# boilup_v2.net
KiCad netlist of a schematic drawn in EAGLE
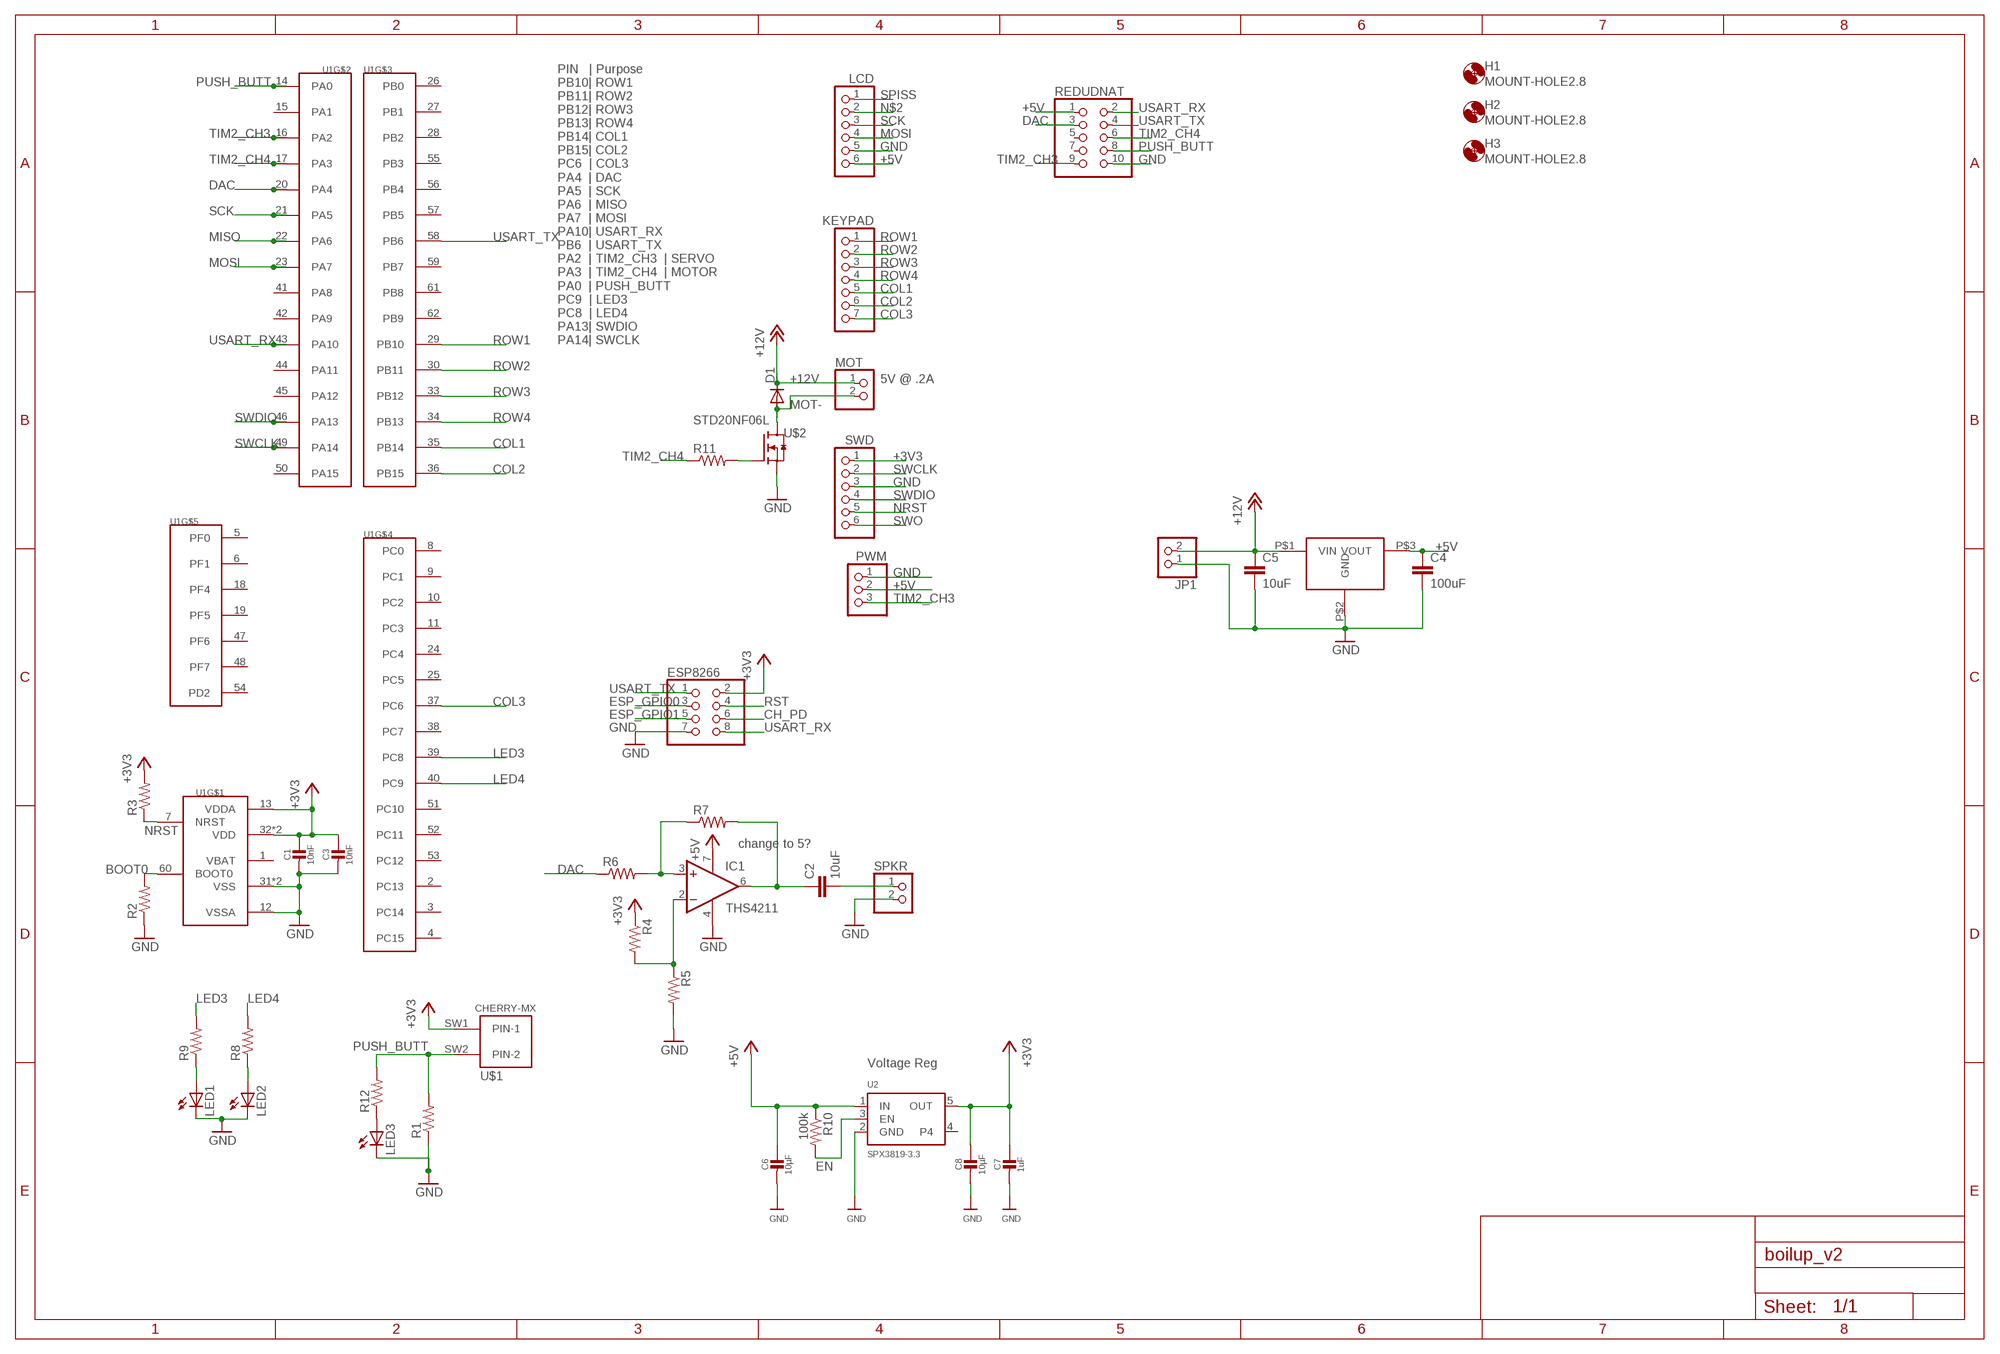
[diagram p0: schematic, sheet 1]

(export (version "E")
  (design (tool "Eeschema 10.0.6"))
  (components
    (comp (ref "C1")
      (value "10nF")
      (footprint "eagle-import:0805-NO")
      (libsource (lib "eagle-import") (part "CAP_CERAMIC0805-NOOUTLINE"))
    )
    (comp (ref "C2")
      (value "10uF")
      (footprint "eagle-import:C0603K")
      (libsource (lib "eagle-import") (part "C-EUC0603K"))
    )
    (comp (ref "C3")
      (value "10nF")
      (footprint "eagle-import:0805-NO")
      (libsource (lib "eagle-import") (part "CAP_CERAMIC0805-NOOUTLINE"))
    )
    (comp (ref "C4")
      (value "100uF")
      (footprint "eagle-import:C1210K")
      (libsource (lib "eagle-import") (part "C-EUC1210K"))
    )
    (comp (ref "C5")
      (value "10uF")
      (footprint "eagle-import:C0603K")
      (libsource (lib "eagle-import") (part "C-EUC0603K"))
    )
    (comp (ref "C6")
      (value "10µF")
      (footprint "eagle-import:0805-NO")
      (libsource (lib "eagle-import") (part "CAP_CERAMIC0805-NOOUTLINE"))
    )
    (comp (ref "C7")
      (value "1uF")
      (footprint "eagle-import:0603-NO")
      (libsource (lib "eagle-import") (part "CAP_CERAMIC0603_NO"))
    )
    (comp (ref "C8")
      (value "10µF")
      (footprint "eagle-import:0805-NO")
      (libsource (lib "eagle-import") (part "CAP_CERAMIC0805-NOOUTLINE"))
    )
    (comp (ref "D1")
      (value "DIODE-DO-214AC")
      (footprint "eagle-import:DO-214AC")
      (libsource (lib "eagle-import") (part "DIODE-DO-214AC"))
    )
    (comp (ref "ESP8266")
      (value "PINHD-2X4")
      (footprint "eagle-import:2X04")
      (libsource (lib "eagle-import") (part "PINHD-2X4"))
    )
    (comp (ref "H1")
      (value "MOUNT-HOLE2.8")
      (footprint "eagle-import:2,8")
      (libsource (lib "eagle-import") (part "MOUNT-HOLE2.8"))
    )
    (comp (ref "H2")
      (value "MOUNT-HOLE2.8")
      (footprint "eagle-import:2,8")
      (libsource (lib "eagle-import") (part "MOUNT-HOLE2.8"))
    )
    (comp (ref "H3")
      (value "MOUNT-HOLE2.8")
      (footprint "eagle-import:2,8")
      (libsource (lib "eagle-import") (part "MOUNT-HOLE2.8"))
    )
    (comp (ref "IC1")
      (value "THS4211")
      (footprint "eagle-import:S-PDSO-G08")
      (fields (field (name "MF") "TEXAS INSTRUMENT CONNECTORS") (field (name "MPN") "THS4211DGK"))
      (libsource (lib "eagle-import") (part "THS4211"))
    )
    (comp (ref "JP1")
      (value "PINHD-1X2")
      (footprint "eagle-import:1X02")
      (libsource (lib "eagle-import") (part "PINHD-1X2"))
    )
    (comp (ref "KEYPAD")
      (value "PINHD-1X7")
      (footprint "eagle-import:1X07")
      (libsource (lib "eagle-import") (part "PINHD-1X7"))
    )
    (comp (ref "LCD")
      (value "PINHD-1X6")
      (footprint "eagle-import:1X06")
      (libsource (lib "eagle-import") (part "PINHD-1X6"))
    )
    (comp (ref "LED1")
      (value "LEDSML0805")
      (footprint "eagle-import:SML0805")
      (libsource (lib "eagle-import") (part "LEDSML0805"))
    )
    (comp (ref "LED2")
      (value "LEDSML0805")
      (footprint "eagle-import:SML0805")
      (libsource (lib "eagle-import") (part "LEDSML0805"))
    )
    (comp (ref "LED3")
      (value "LEDSML0805")
      (footprint "eagle-import:SML0805")
      (libsource (lib "eagle-import") (part "LEDSML0805"))
    )
    (comp (ref "MOT")
      (value "PINHD-1X2")
      (footprint "eagle-import:1X02")
      (libsource (lib "eagle-import") (part "PINHD-1X2"))
    )
    (comp (ref "PWM")
      (value "PINHD-1X3")
      (footprint "eagle-import:1X03")
      (libsource (lib "eagle-import") (part "PINHD-1X3"))
    )
    (comp (ref "R1")
      (value "R-US_R0603")
      (footprint "eagle-import:R0603")
      (libsource (lib "eagle-import") (part "resistor_348_R-US_R0603"))
    )
    (comp (ref "R2")
      (value "R-US_R0603")
      (footprint "eagle-import:R0603")
      (libsource (lib "eagle-import") (part "resistor_348_R-US_R0603"))
    )
    (comp (ref "R3")
      (value "R-US_R0603")
      (footprint "eagle-import:R0603")
      (libsource (lib "eagle-import") (part "resistor_348_R-US_R0603"))
    )
    (comp (ref "R4")
      (value "R-US_R0603")
      (footprint "eagle-import:R0603")
      (libsource (lib "eagle-import") (part "resistor_348_R-US_R0603"))
    )
    (comp (ref "R5")
      (value "R-US_R0603")
      (footprint "eagle-import:R0603")
      (libsource (lib "eagle-import") (part "resistor_348_R-US_R0603"))
    )
    (comp (ref "R6")
      (value "R-US_R0603")
      (footprint "eagle-import:R0603")
      (libsource (lib "eagle-import") (part "resistor_348_R-US_R0603"))
    )
    (comp (ref "R7")
      (value "R-US_R0603")
      (footprint "eagle-import:R0603")
      (libsource (lib "eagle-import") (part "resistor_348_R-US_R0603"))
    )
    (comp (ref "R8")
      (value "R-US_R0603")
      (footprint "eagle-import:R0603")
      (libsource (lib "eagle-import") (part "resistor_348_R-US_R0603"))
    )
    (comp (ref "R9")
      (value "R-US_R0603")
      (footprint "eagle-import:R0603")
      (libsource (lib "eagle-import") (part "resistor_348_R-US_R0603"))
    )
    (comp (ref "R10")
      (value "100k")
      (footprint "eagle-import:R0603")
      (libsource (lib "eagle-import") (part "R-US_R0603"))
    )
    (comp (ref "R11")
      (value "R-US_R0603")
      (footprint "eagle-import:R0603")
      (libsource (lib "eagle-import") (part "resistor_348_R-US_R0603"))
    )
    (comp (ref "R12")
      (value "R-US_R0603")
      (footprint "eagle-import:R0603")
      (libsource (lib "eagle-import") (part "resistor_348_R-US_R0603"))
    )
    (comp (ref "REDUDNAT")
      (value "PINHD-2X5")
      (footprint "eagle-import:2X05")
      (libsource (lib "eagle-import") (part "PINHD-2X5"))
    )
    (comp (ref "SPKR")
      (value "PINHD-1X2")
      (footprint "eagle-import:1X02")
      (libsource (lib "eagle-import") (part "PINHD-1X2"))
    )
    (comp (ref "SWD")
      (value "PINHD-1X6")
      (footprint "eagle-import:1X06")
      (libsource (lib "eagle-import") (part "PINHD-1X6"))
    )
    (comp (ref "U$1")
      (value "CHERRY-MX")
      (footprint "eagle-import:CHERRY-MX")
      (libsource (lib "eagle-import") (part "CHERRY-MX"))
    )
    (comp (ref "U$2")
      (value "STD20NF06L")
      (footprint "eagle-import:DPAK")
      (libsource (lib "eagle-import") (part "STD20NF06L"))
    )
    (comp (ref "U$3")
      (value "TPSM842")
      (footprint "eagle-import:TO-220")
      (libsource (lib "eagle-import") (part "TPSM842"))
    )
    (comp (ref "U1")
      (value "STM32F0_LQFP64")
      (footprint "eagle-import:QFP50P1200X1200X160-64N")
      (libsource (lib "eagle-import") (part "STM32F0_LQFP64"))
    )
    (comp (ref "U2")
      (value "SPX3819-3.3")
      (footprint "eagle-import:SOT23-5")
      (libsource (lib "eagle-import") (part "VREG_SOT23-5"))
    )
  )
  (nets
    (net (code "1") (name "+3V3") (class "Default")
      (node (ref "C1") (pin "1") (pinfunction "1_1") (pintype "passive"))
      (node (ref "C3") (pin "1") (pinfunction "1_1") (pintype "passive"))
      (node (ref "C7") (pin "1") (pinfunction "1_1") (pintype "passive"))
      (node (ref "C8") (pin "1") (pinfunction "1_1") (pintype "passive"))
      (node (ref "ESP8266") (pin "2") (pinfunction "2_2") (pintype "passive"))
      (node (ref "R3") (pin "2") (pinfunction "2_2") (pintype "passive"))
      (node (ref "R4") (pin "1") (pinfunction "1_1") (pintype "passive"))
      (node (ref "SWD") (pin "1") (pinfunction "1_1") (pintype "passive"))
      (node (ref "U$1") (pin "SW1") (pinfunction "PIN-1_SW1") (pintype "bidirectional"))
      (node (ref "U1") (pin "13") (pinfunction "VDDA_13") (pintype "bidirectional"))
      (node (ref "U1") (pin "32") (pinfunction "VDD_32") (pintype "bidirectional"))
      (node (ref "U1") (pin "64") (pinfunction "VDD_64") (pintype "bidirectional"))
      (node (ref "U2") (pin "5") (pinfunction "OUT_5") (pintype "power_in"))
    )
    (net (code "2") (name "+5V") (class "Default")
      (node (ref "C4") (pin "1") (pinfunction "1_1") (pintype "passive"))
      (node (ref "C6") (pin "1") (pinfunction "1_1") (pintype "passive"))
      (node (ref "IC1") (pin "7") (pinfunction "V+_7") (pintype "power_in"))
      (node (ref "LCD") (pin "6") (pinfunction "6_6") (pintype "passive"))
      (node (ref "PWM") (pin "2") (pinfunction "2_2") (pintype "passive"))
      (node (ref "R10") (pin "1") (pinfunction "1_1") (pintype "passive"))
      (node (ref "REDUDNAT") (pin "1") (pinfunction "1_1") (pintype "passive"))
      (node (ref "U$3") (pin "P$3") (pinfunction "VOUT_P$3") (pintype "bidirectional"))
      (node (ref "U2") (pin "1") (pinfunction "IN_1") (pintype "power_in"))
    )
    (net (code "3") (name "+12V") (class "Default")
      (node (ref "C5") (pin "1") (pinfunction "1_1") (pintype "passive"))
      (node (ref "D1") (pin "C") (pinfunction "C_C") (pintype "passive"))
      (node (ref "JP1") (pin "2") (pinfunction "2_2") (pintype "passive"))
      (node (ref "MOT") (pin "1") (pinfunction "1_1") (pintype "passive"))
      (node (ref "U$3") (pin "P$1") (pinfunction "VIN_P$1") (pintype "bidirectional"))
    )
    (net (code "4") (name "/BOOT0") (class "Default")
      (node (ref "R2") (pin "2") (pinfunction "2_2") (pintype "passive"))
      (node (ref "U1") (pin "60") (pinfunction "BOOT0_60") (pintype "bidirectional"))
    )
    (net (code "5") (name "/CH_PD") (class "Default")
      (node (ref "ESP8266") (pin "6") (pinfunction "6_6") (pintype "passive"))
    )
    (net (code "6") (name "/COL1") (class "Default")
      (node (ref "KEYPAD") (pin "5") (pinfunction "5_5") (pintype "passive"))
      (node (ref "U1") (pin "35") (pinfunction "PB14_35") (pintype "bidirectional"))
    )
    (net (code "7") (name "/COL2") (class "Default")
      (node (ref "KEYPAD") (pin "6") (pinfunction "6_6") (pintype "passive"))
      (node (ref "U1") (pin "36") (pinfunction "PB15_36") (pintype "bidirectional"))
    )
    (net (code "8") (name "/COL3") (class "Default")
      (node (ref "KEYPAD") (pin "7") (pinfunction "7_7") (pintype "passive"))
      (node (ref "U1") (pin "37") (pinfunction "PC6_37") (pintype "bidirectional"))
    )
    (net (code "9") (name "/DAC") (class "Default")
      (node (ref "R6") (pin "1") (pinfunction "1_1") (pintype "passive"))
      (node (ref "REDUDNAT") (pin "3") (pinfunction "3_3") (pintype "passive"))
      (node (ref "U1") (pin "20") (pinfunction "PA4_20") (pintype "bidirectional"))
    )
    (net (code "10") (name "/EN") (class "Default")
      (node (ref "R10") (pin "2") (pinfunction "2_2") (pintype "passive"))
      (node (ref "U2") (pin "3") (pinfunction "EN_3") (pintype "input"))
    )
    (net (code "11") (name "/ESP_GPIO0") (class "Default")
      (node (ref "ESP8266") (pin "3") (pinfunction "3_3") (pintype "passive"))
    )
    (net (code "12") (name "/ESP_GPIO1") (class "Default")
      (node (ref "ESP8266") (pin "5") (pinfunction "5_5") (pintype "passive"))
    )
    (net (code "13") (name "/LED3") (class "Default")
      (node (ref "R9") (pin "2") (pinfunction "2_2") (pintype "passive"))
      (node (ref "U1") (pin "39") (pinfunction "PC8_39") (pintype "bidirectional"))
    )
    (net (code "14") (name "/LED4") (class "Default")
      (node (ref "R8") (pin "2") (pinfunction "2_2") (pintype "passive"))
      (node (ref "U1") (pin "40") (pinfunction "PC9_40") (pintype "bidirectional"))
    )
    (net (code "15") (name "/MISO") (class "Default")
      (node (ref "U1") (pin "22") (pinfunction "PA6_22") (pintype "bidirectional"))
    )
    (net (code "16") (name "/MOSI") (class "Default")
      (node (ref "LCD") (pin "4") (pinfunction "4_4") (pintype "passive"))
      (node (ref "U1") (pin "23") (pinfunction "PA7_23") (pintype "bidirectional"))
    )
    (net (code "17") (name "/MOT-") (class "Default")
      (node (ref "D1") (pin "A") (pinfunction "A_A") (pintype "passive"))
      (node (ref "MOT") (pin "2") (pinfunction "2_2") (pintype "passive"))
      (node (ref "U$2") (pin "P$1") (pinfunction "D_P$1") (pintype "passive"))
    )
    (net (code "18") (name "/N$2") (class "Default")
      (node (ref "LCD") (pin "2") (pinfunction "2_2") (pintype "passive"))
    )
    (net (code "19") (name "/NRST") (class "Default")
      (node (ref "R3") (pin "1") (pinfunction "1_1") (pintype "passive"))
      (node (ref "SWD") (pin "5") (pinfunction "5_5") (pintype "passive"))
      (node (ref "U1") (pin "7") (pinfunction "NRST_7") (pintype "bidirectional"))
    )
    (net (code "20") (name "/PUSH_BUTT") (class "Default")
      (node (ref "R1") (pin "2") (pinfunction "2_2") (pintype "passive"))
      (node (ref "R12") (pin "2") (pinfunction "2_2") (pintype "passive"))
      (node (ref "REDUDNAT") (pin "8") (pinfunction "8_8") (pintype "passive"))
      (node (ref "U$1") (pin "SW2") (pinfunction "PIN-2_SW2") (pintype "bidirectional"))
      (node (ref "U1") (pin "14") (pinfunction "PA0_14") (pintype "bidirectional"))
    )
    (net (code "21") (name "/ROW1") (class "Default")
      (node (ref "KEYPAD") (pin "1") (pinfunction "1_1") (pintype "passive"))
      (node (ref "U1") (pin "29") (pinfunction "PB10_29") (pintype "bidirectional"))
    )
    (net (code "22") (name "/ROW2") (class "Default")
      (node (ref "KEYPAD") (pin "2") (pinfunction "2_2") (pintype "passive"))
      (node (ref "U1") (pin "30") (pinfunction "PB11_30") (pintype "bidirectional"))
    )
    (net (code "23") (name "/ROW3") (class "Default")
      (node (ref "KEYPAD") (pin "3") (pinfunction "3_3") (pintype "passive"))
      (node (ref "U1") (pin "33") (pinfunction "PB12_33") (pintype "bidirectional"))
    )
    (net (code "24") (name "/ROW4") (class "Default")
      (node (ref "KEYPAD") (pin "4") (pinfunction "4_4") (pintype "passive"))
      (node (ref "U1") (pin "34") (pinfunction "PB13_34") (pintype "bidirectional"))
    )
    (net (code "25") (name "/RST") (class "Default")
      (node (ref "ESP8266") (pin "4") (pinfunction "4_4") (pintype "passive"))
    )
    (net (code "26") (name "/SCK") (class "Default")
      (node (ref "LCD") (pin "3") (pinfunction "3_3") (pintype "passive"))
      (node (ref "U1") (pin "21") (pinfunction "PA5_21") (pintype "bidirectional"))
    )
    (net (code "27") (name "/SPISS") (class "Default")
      (node (ref "LCD") (pin "1") (pinfunction "1_1") (pintype "passive"))
    )
    (net (code "28") (name "/SWCLK") (class "Default")
      (node (ref "SWD") (pin "2") (pinfunction "2_2") (pintype "passive"))
      (node (ref "U1") (pin "49") (pinfunction "PA14_49") (pintype "bidirectional"))
    )
    (net (code "29") (name "/SWDIO") (class "Default")
      (node (ref "SWD") (pin "4") (pinfunction "4_4") (pintype "passive"))
      (node (ref "U1") (pin "46") (pinfunction "PA13_46") (pintype "bidirectional"))
    )
    (net (code "30") (name "/SWO") (class "Default")
      (node (ref "SWD") (pin "6") (pinfunction "6_6") (pintype "passive"))
    )
    (net (code "31") (name "/TIM2_CH3") (class "Default")
      (node (ref "PWM") (pin "3") (pinfunction "3_3") (pintype "passive"))
      (node (ref "REDUDNAT") (pin "9") (pinfunction "9_9") (pintype "passive"))
      (node (ref "U1") (pin "16") (pinfunction "PA2_16") (pintype "bidirectional"))
    )
    (net (code "32") (name "/TIM2_CH4") (class "Default")
      (node (ref "R11") (pin "1") (pinfunction "1_1") (pintype "passive"))
      (node (ref "REDUDNAT") (pin "6") (pinfunction "6_6") (pintype "passive"))
      (node (ref "U1") (pin "17") (pinfunction "PA3_17") (pintype "bidirectional"))
    )
    (net (code "33") (name "/USART_RX") (class "Default")
      (node (ref "ESP8266") (pin "8") (pinfunction "8_8") (pintype "passive"))
      (node (ref "REDUDNAT") (pin "2") (pinfunction "2_2") (pintype "passive"))
      (node (ref "U1") (pin "43") (pinfunction "PA10_43") (pintype "bidirectional"))
    )
    (net (code "34") (name "/USART_TX") (class "Default")
      (node (ref "ESP8266") (pin "1") (pinfunction "1_1") (pintype "passive"))
      (node (ref "REDUDNAT") (pin "4") (pinfunction "4_4") (pintype "passive"))
      (node (ref "U1") (pin "58") (pinfunction "PB6_58") (pintype "bidirectional"))
    )
    (net (code "35") (name "GND") (class "Default")
      (node (ref "C1") (pin "2") (pinfunction "2_2") (pintype "passive"))
      (node (ref "C3") (pin "2") (pinfunction "2_2") (pintype "passive"))
      (node (ref "C4") (pin "2") (pinfunction "2_2") (pintype "passive"))
      (node (ref "C5") (pin "2") (pinfunction "2_2") (pintype "passive"))
      (node (ref "C6") (pin "2") (pinfunction "2_2") (pintype "passive"))
      (node (ref "C7") (pin "2") (pinfunction "2_2") (pintype "passive"))
      (node (ref "C8") (pin "2") (pinfunction "2_2") (pintype "passive"))
      (node (ref "ESP8266") (pin "7") (pinfunction "7_7") (pintype "passive"))
      (node (ref "IC1") (pin "4") (pinfunction "V-_4") (pintype "power_in"))
      (node (ref "JP1") (pin "1") (pinfunction "1_1") (pintype "passive"))
      (node (ref "LCD") (pin "5") (pinfunction "5_5") (pintype "passive"))
      (node (ref "LED1") (pin "C") (pinfunction "C_C") (pintype "passive"))
      (node (ref "LED2") (pin "C") (pinfunction "C_C") (pintype "passive"))
      (node (ref "LED3") (pin "C") (pinfunction "C_C") (pintype "passive"))
      (node (ref "PWM") (pin "1") (pinfunction "1_1") (pintype "passive"))
      (node (ref "R1") (pin "1") (pinfunction "1_1") (pintype "passive"))
      (node (ref "R2") (pin "1") (pinfunction "1_1") (pintype "passive"))
      (node (ref "R5") (pin "2") (pinfunction "2_2") (pintype "passive"))
      (node (ref "REDUDNAT") (pin "10") (pinfunction "10_10") (pintype "passive"))
      (node (ref "SPKR") (pin "2") (pinfunction "2_2") (pintype "passive"))
      (node (ref "SWD") (pin "3") (pinfunction "3_3") (pintype "passive"))
      (node (ref "U$2") (pin "P$2") (pinfunction "S_P$2") (pintype "passive"))
      (node (ref "U$3") (pin "P$2") (pinfunction "GND_P$2") (pintype "bidirectional"))
      (node (ref "U1") (pin "12") (pinfunction "VSSA_12") (pintype "bidirectional"))
      (node (ref "U1") (pin "31") (pinfunction "VSS_31") (pintype "bidirectional"))
      (node (ref "U1") (pin "63") (pinfunction "VSS_63") (pintype "bidirectional"))
      (node (ref "U2") (pin "2") (pinfunction "GND_2") (pintype "power_in"))
    )
    (net (code "36") (name "Net-(C2-Pad2)") (class "Default")
      (node (ref "C2") (pin "2") (pinfunction "2_2") (pintype "passive"))
      (node (ref "SPKR") (pin "1") (pinfunction "1_1") (pintype "passive"))
    )
    (net (code "37") (name "Net-(IC1A-+IN)") (class "Default")
      (node (ref "IC1") (pin "3") (pinfunction "+IN_3") (pintype "input"))
      (node (ref "R6") (pin "2") (pinfunction "2_2") (pintype "passive"))
      (node (ref "R7") (pin "1") (pinfunction "1_1") (pintype "passive"))
    )
    (net (code "38") (name "Net-(IC1A--IN)") (class "Default")
      (node (ref "IC1") (pin "2") (pinfunction "-IN_2") (pintype "input"))
      (node (ref "R4") (pin "2") (pinfunction "2_2") (pintype "passive"))
      (node (ref "R5") (pin "1") (pinfunction "1_1") (pintype "passive"))
    )
    (net (code "39") (name "Net-(IC1A-OUT)") (class "Default")
      (node (ref "C2") (pin "1") (pinfunction "1_1") (pintype "passive"))
      (node (ref "IC1") (pin "6") (pinfunction "OUT_6") (pintype "output"))
      (node (ref "R7") (pin "2") (pinfunction "2_2") (pintype "passive"))
    )
    (net (code "40") (name "Net-(LED1-PadA)") (class "Default")
      (node (ref "LED1") (pin "A") (pinfunction "A_A") (pintype "passive"))
      (node (ref "R9") (pin "1") (pinfunction "1_1") (pintype "passive"))
    )
    (net (code "41") (name "Net-(LED2-PadA)") (class "Default")
      (node (ref "LED2") (pin "A") (pinfunction "A_A") (pintype "passive"))
      (node (ref "R8") (pin "1") (pinfunction "1_1") (pintype "passive"))
    )
    (net (code "42") (name "Net-(LED3-PadA)") (class "Default")
      (node (ref "LED3") (pin "A") (pinfunction "A_A") (pintype "passive"))
      (node (ref "R12") (pin "1") (pinfunction "1_1") (pintype "passive"))
    )
    (net (code "43") (name "Net-(U$2-G)") (class "Default")
      (node (ref "R11") (pin "2") (pinfunction "2_2") (pintype "passive"))
      (node (ref "U$2") (pin "P$3") (pinfunction "G_P$3") (pintype "passive"))
    )
    (net (code "44") (name "unconnected-(REDUDNAT-Pad5)") (class "Default")
      (node (ref "REDUDNAT") (pin "5") (pinfunction "5_5") (pintype "passive"))
    )
    (net (code "45") (name "unconnected-(REDUDNAT-Pad7)") (class "Default")
      (node (ref "REDUDNAT") (pin "7") (pinfunction "7_7") (pintype "passive"))
    )
    (net (code "46") (name "unconnected-(U1A-VBAT-Pad1)") (class "Default")
      (node (ref "U1") (pin "1") (pinfunction "VBAT_1") (pintype "bidirectional"))
    )
    (net (code "47") (name "unconnected-(U1B-PA1-Pad15)") (class "Default")
      (node (ref "U1") (pin "15") (pinfunction "PA1_15") (pintype "bidirectional"))
    )
    (net (code "48") (name "unconnected-(U1B-PA8-Pad41)") (class "Default")
      (node (ref "U1") (pin "41") (pinfunction "PA8_41") (pintype "bidirectional"))
    )
    (net (code "49") (name "unconnected-(U1B-PA9-Pad42)") (class "Default")
      (node (ref "U1") (pin "42") (pinfunction "PA9_42") (pintype "bidirectional"))
    )
    (net (code "50") (name "unconnected-(U1B-PA11-Pad44)") (class "Default")
      (node (ref "U1") (pin "44") (pinfunction "PA11_44") (pintype "bidirectional"))
    )
    (net (code "51") (name "unconnected-(U1B-PA12-Pad45)") (class "Default")
      (node (ref "U1") (pin "45") (pinfunction "PA12_45") (pintype "bidirectional"))
    )
    (net (code "52") (name "unconnected-(U1B-PA15-Pad50)") (class "Default")
      (node (ref "U1") (pin "50") (pinfunction "PA15_50") (pintype "bidirectional"))
    )
    (net (code "53") (name "unconnected-(U1C-PB0-Pad26)") (class "Default")
      (node (ref "U1") (pin "26") (pinfunction "PB0_26") (pintype "bidirectional"))
    )
    (net (code "54") (name "unconnected-(U1C-PB1-Pad27)") (class "Default")
      (node (ref "U1") (pin "27") (pinfunction "PB1_27") (pintype "bidirectional"))
    )
    (net (code "55") (name "unconnected-(U1C-PB2-Pad28)") (class "Default")
      (node (ref "U1") (pin "28") (pinfunction "PB2_28") (pintype "bidirectional"))
    )
    (net (code "56") (name "unconnected-(U1C-PB3-Pad55)") (class "Default")
      (node (ref "U1") (pin "55") (pinfunction "PB3_55") (pintype "bidirectional"))
    )
    (net (code "57") (name "unconnected-(U1C-PB4-Pad56)") (class "Default")
      (node (ref "U1") (pin "56") (pinfunction "PB4_56") (pintype "bidirectional"))
    )
    (net (code "58") (name "unconnected-(U1C-PB5-Pad57)") (class "Default")
      (node (ref "U1") (pin "57") (pinfunction "PB5_57") (pintype "bidirectional"))
    )
    (net (code "59") (name "unconnected-(U1C-PB7-Pad59)") (class "Default")
      (node (ref "U1") (pin "59") (pinfunction "PB7_59") (pintype "bidirectional"))
    )
    (net (code "60") (name "unconnected-(U1C-PB8-Pad61)") (class "Default")
      (node (ref "U1") (pin "61") (pinfunction "PB8_61") (pintype "bidirectional"))
    )
    (net (code "61") (name "unconnected-(U1C-PB9-Pad62)") (class "Default")
      (node (ref "U1") (pin "62") (pinfunction "PB9_62") (pintype "bidirectional"))
    )
    (net (code "62") (name "unconnected-(U1D-PC0-Pad8)") (class "Default")
      (node (ref "U1") (pin "8") (pinfunction "PC0_8") (pintype "bidirectional"))
    )
    (net (code "63") (name "unconnected-(U1D-PC1-Pad9)") (class "Default")
      (node (ref "U1") (pin "9") (pinfunction "PC1_9") (pintype "bidirectional"))
    )
    (net (code "64") (name "unconnected-(U1D-PC2-Pad10)") (class "Default")
      (node (ref "U1") (pin "10") (pinfunction "PC2_10") (pintype "bidirectional"))
    )
    (net (code "65") (name "unconnected-(U1D-PC3-Pad11)") (class "Default")
      (node (ref "U1") (pin "11") (pinfunction "PC3_11") (pintype "bidirectional"))
    )
    (net (code "66") (name "unconnected-(U1D-PC4-Pad24)") (class "Default")
      (node (ref "U1") (pin "24") (pinfunction "PC4_24") (pintype "bidirectional"))
    )
    (net (code "67") (name "unconnected-(U1D-PC5-Pad25)") (class "Default")
      (node (ref "U1") (pin "25") (pinfunction "PC5_25") (pintype "bidirectional"))
    )
    (net (code "68") (name "unconnected-(U1D-PC7-Pad38)") (class "Default")
      (node (ref "U1") (pin "38") (pinfunction "PC7_38") (pintype "bidirectional"))
    )
    (net (code "69") (name "unconnected-(U1D-PC10-Pad51)") (class "Default")
      (node (ref "U1") (pin "51") (pinfunction "PC10_51") (pintype "bidirectional"))
    )
    (net (code "70") (name "unconnected-(U1D-PC11-Pad52)") (class "Default")
      (node (ref "U1") (pin "52") (pinfunction "PC11_52") (pintype "bidirectional"))
    )
    (net (code "71") (name "unconnected-(U1D-PC12-Pad53)") (class "Default")
      (node (ref "U1") (pin "53") (pinfunction "PC12_53") (pintype "bidirectional"))
    )
    (net (code "72") (name "unconnected-(U1D-PC13-Pad2)") (class "Default")
      (node (ref "U1") (pin "2") (pinfunction "PC13_2") (pintype "bidirectional"))
    )
    (net (code "73") (name "unconnected-(U1D-PC14-Pad3)") (class "Default")
      (node (ref "U1") (pin "3") (pinfunction "PC14_3") (pintype "bidirectional"))
    )
    (net (code "74") (name "unconnected-(U1D-PC15-Pad4)") (class "Default")
      (node (ref "U1") (pin "4") (pinfunction "PC15_4") (pintype "bidirectional"))
    )
    (net (code "75") (name "unconnected-(U1E-PD2-Pad54)") (class "Default")
      (node (ref "U1") (pin "54") (pinfunction "PD2_54") (pintype "bidirectional"))
    )
    (net (code "76") (name "unconnected-(U1E-PF0-Pad5)") (class "Default")
      (node (ref "U1") (pin "5") (pinfunction "PF0_5") (pintype "bidirectional"))
    )
    (net (code "77") (name "unconnected-(U1E-PF1-Pad6)") (class "Default")
      (node (ref "U1") (pin "6") (pinfunction "PF1_6") (pintype "bidirectional"))
    )
    (net (code "78") (name "unconnected-(U1E-PF4-Pad18)") (class "Default")
      (node (ref "U1") (pin "18") (pinfunction "PF4_18") (pintype "bidirectional"))
    )
    (net (code "79") (name "unconnected-(U1E-PF5-Pad19)") (class "Default")
      (node (ref "U1") (pin "19") (pinfunction "PF5_19") (pintype "bidirectional"))
    )
    (net (code "80") (name "unconnected-(U1E-PF6-Pad47)") (class "Default")
      (node (ref "U1") (pin "47") (pinfunction "PF6_47") (pintype "bidirectional"))
    )
    (net (code "81") (name "unconnected-(U1E-PF7-Pad48)") (class "Default")
      (node (ref "U1") (pin "48") (pinfunction "PF7_48") (pintype "bidirectional"))
    )
    (net (code "82") (name "unconnected-(U2-P4-Pad4)") (class "Default")
      (node (ref "U2") (pin "4") (pinfunction "P4_4") (pintype "bidirectional"))
    )
  )
)
